# ledDriverSchematic.net
KiCad netlist of a schematic drawn in Altium Designer
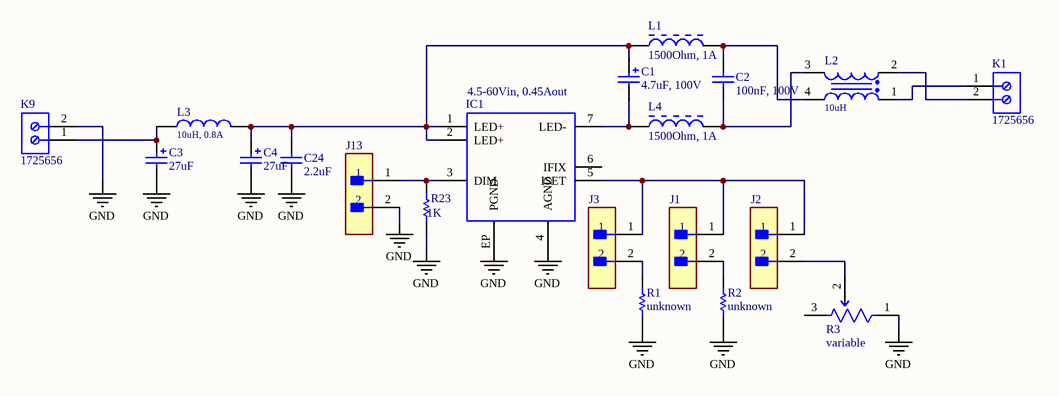
[diagram p0: ledDriverSchematic.SchDoc]

(export (version "E")
  (design (tool "Eeschema 10.0.6"))
  (components
    (comp (ref "C1")
      (value "4.7uF, 100V")
      (footprint "WCAP-PSLP_D6.3H7.7")
      (description "WCAP-PSLP Aluminum Polymer Capacitor, V-Chip, SMT, D6.3xH7.7mm, 4.7uF, 100V")
      (fields
        (field (name "MANUFACTURER PART NUMBER") "875105945001")
        (field (name "MANUFACTURER") "Wurth Elektronik")
      )
      (libsource (lib "Altium_WCAP-PSLP (rev20b)") (part "875105945001"))
    )
    (comp (ref "C2")
      (value "100nF, 100V")
      (footprint "WCAP-CSGP_0805_H=1.25mm")
      (description "WCAP-CSGP Multilayer Ceramic Chip Capacitor, General Purpose, size 0805, X7R, 100nF, 100V")
      (fields
        (field (name "MANUFACTURER PART NUMBER") "885012207128")
        (field (name "MANUFACTURER") "Wurth Elektronik")
      )
      (libsource (lib "Altium_WCAP-CSGP (rev21a)") (part "885012207128"))
    )
    (comp (ref "C3")
      (value "27uF")
      (footprint "WCAP-ATUL_D8H11.5")
      (description "WCAP-ATUL Aluminum Electrolytic Capacitor, Radial, THT, D8xH11.5mm, 27uF, 100V")
      (fields
        (field (name "MANUFACTURER") "Wurth Elektronik")
        (field (name "MANUFACTURER PART NUMBER") "860040874001")
      )
      (libsource (lib "Altium_WCAP-ATUL (rev20b)") (part "860040874001"))
    )
    (comp (ref "C4")
      (value "27uF")
      (footprint "WCAP-ATUL_D8H11.5")
      (description "WCAP-ATUL Aluminum Electrolytic Capacitor, Radial, THT, D8xH11.5mm, 27uF, 100V")
      (fields
        (field (name "MANUFACTURER") "Wurth Elektronik")
        (field (name "MANUFACTURER PART NUMBER") "860040874001")
      )
      (libsource (lib "Altium_WCAP-ATUL (rev20b)") (part "860040874001"))
    )
    (comp (ref "C24")
      (value "2.2uF")
      (footprint "CAPC1210(3225)280_N")
      (description "CAP 2.2uF 100V ±10% 1210 (3225 Metric) Thickness 2.8mm SMD")
      (fields (field (name "TOLERANCE") "Â±10%"))
      (libsource (lib "Altium Content Vault") (part "CAP"))
    )
    (comp (ref "IC1")
      (value "4.5-60Vin, 0.45Aout")
      (footprint "172946001")
      (description "MagI3C-LDHM LED Step Down High Current Module, TO263-7EP, 4.5-60Vin, 0.45Aout")
      (fields (field (name "PART NUMBER") "172946001") (field (name "PUBLISHER") "Wurth Elektronik"))
      (libsource (lib "Altium_MAGIC-LDHM (rev19a)") (part "172946001"))
    )
    (comp (ref "J1")
      (value "~")
      (footprint "FP-TSW-102-07-G-S-MFG")
      (description "CONN HEADER VERT 2POS 2.54MM")
      (fields
        (field (name "MANUFACTURER") "Samtec")
        (field (name "MANUFACTURER PART NUMBER") "TSW-102-07-G-S")
      )
      (libsource (lib "Altium Content Vault") (part "3bc925449376181038e59eaffc5286c"))
    )
    (comp (ref "J2")
      (value "~")
      (footprint "FP-TSW-102-07-G-S-MFG")
      (description "CONN HEADER VERT 2POS 2.54MM")
      (fields
        (field (name "MANUFACTURER") "Samtec")
        (field (name "MANUFACTURER PART NUMBER") "TSW-102-07-G-S")
      )
      (libsource (lib "Altium Content Vault") (part "3bc925449376181038e59eaffc5286c"))
    )
    (comp (ref "J3")
      (value "~")
      (footprint "FP-TSW-102-07-G-S-MFG")
      (description "CONN HEADER VERT 2POS 2.54MM")
      (fields
        (field (name "MANUFACTURER") "Samtec")
        (field (name "MANUFACTURER PART NUMBER") "TSW-102-07-G-S")
      )
      (libsource (lib "Altium Content Vault") (part "3bc925449376181038e59eaffc5286c"))
    )
    (comp (ref "J13")
      (value "~")
      (footprint "FP-TSW-102-07-G-S-MFG")
      (description "CONN HEADER VERT 2POS 2.54MM")
      (fields
        (field (name "MANUFACTURER") "Samtec")
        (field (name "MANUFACTURER PART NUMBER") "TSW-102-07-G-S")
      )
      (libsource (lib "Altium Content Vault") (part "3bc925449376181038e59eaffc5286c"))
    )
    (comp (ref "K1")
      (value "1725656")
      (footprint "PHOE-1725656-2")
      (description "Male Header, Pitch 2.54 mm, 1 x 2 Position, Height 9 mm, Tail Length 3.5 mm")
      (fields (field (name "MANUFACTURER") "Phoenix Contact"))
      (libsource (lib "Altium Content Vault") (part "CN-1P-F-TB2"))
    )
    (comp (ref "K9")
      (value "1725656")
      (footprint "PHOE-1725656-2")
      (description "Male Header, Pitch 2.54 mm, 1 x 2 Position, Height 9 mm, Tail Length 3.5 mm")
      (fields (field (name "MANUFACTURER") "Phoenix Contact"))
      (libsource (lib "Altium Content Vault") (part "CN-1P-F-TB2"))
    )
    (comp (ref "L1")
      (value "1500Ohm, 1A")
      (footprint "WE-CBF_0805_High Current")
      (description "WE-CBF SMT EMI Suppression Ferrite Bead, size 0805, 1500Ohm, 1A")
      (fields
        (field (name "MANUFACTURER PART NUMBER") "742792097")
        (field (name "MANUFACTURER") "Wurth Elektronik")
      )
      (libsource (lib "WE-CBF (rev20b)") (part "742792097"))
    )
    (comp (ref "L2")
      (value "10uH")
      (footprint "WE-SL2")
      (description "WE-SL2 SMT Common Mode Line Filter, 10uH, 1.6A, 80V")
      (fields
        (field (name "MANUFACTURER PART NUMBER") "744226S")
        (field (name "MANUFACTURER") "Wurth Elektronik")
      )
      (libsource (lib "WE-SL2 (rev20b)") (part "744226S"))
    )
    (comp (ref "L3")
      (value "10uH, 0.8A")
      (footprint "WE-PD2_3521")
      (description "WE-PD2 SMT Power Inductor, size 3521, 10uH, 0.8A")
      (fields
        (field (name "MANUFACTURER") "Wurth Elektronik")
        (field (name "MANUFACTURER PART NUMBER") "7447732110")
      )
      (libsource (lib "WE-PD2 (rev20a)") (part "7447732110"))
    )
    (comp (ref "L4")
      (value "1500Ohm, 1A")
      (footprint "WE-CBF_0805_High Current")
      (description "WE-CBF SMT EMI Suppression Ferrite Bead, size 0805, 1500Ohm, 1A")
      (fields
        (field (name "MANUFACTURER PART NUMBER") "742792097")
        (field (name "MANUFACTURER") "Wurth Elektronik")
      )
      (libsource (lib "WE-CBF (rev20b)") (part "742792097"))
    )
    (comp (ref "R1")
      (value "unknown")
      (footprint "VISH-A1-2_V2")
      (description "Power Metal Film Leaded Resistor, 62 KOhm +/-5%, 2 W, 2-Pin THD, RoHS, Ammo Pack")
      (fields (field (name "TOLERANCE") "+/-5%") (field (name "POWER") "2 W"))
      (libsource (lib "Altium Content Vault") (part "VISH-RES-2"))
    )
    (comp (ref "R2")
      (value "unknown")
      (footprint "VISH-A1-2_V2")
      (description "Power Metal Film Leaded Resistor, 62 KOhm +/-5%, 2 W, 2-Pin THD, RoHS, Ammo Pack")
      (fields (field (name "TOLERANCE") "+/-5%") (field (name "POWER") "2 W"))
      (libsource (lib "Altium Content Vault") (part "VISH-RES-2"))
    )
    (comp (ref "R3")
      (value "variable")
      (footprint "FP-3361P-MFG")
      (description "TRIMMER 5K OHM 0.5W GW TOP ADJ")
      (fields
        (field (name "OCTOPART") "https://octopart.com/3361p-1-502glf-bourns-92301")
        (field (name "TOLERANCE") "10%")
      )
      (libsource (lib "Altium Content Vault") (part "2dcfd2547301a7d3209a5e99acfd772"))
    )
    (comp (ref "R23")
      (value "1K")
      (footprint "RESC2013X60X30ML20T20")
      (fields (field (name "PART NUMBER") "RK73B2ATTD102J") (field (name "MANUFACTURER") "KOA Speer"))
      (libsource (lib "Altium Content Vault") (part "RES"))
    )
  )
  (nets
    (net (code "1") (name "GND") (class "Default")
      (node (ref "C24") (pin "1") (pinfunction "1_1") (pintype "passive"))
      (node (ref "C3") (pin "2") (pinfunction "N_2") (pintype "passive"))
      (node (ref "C4") (pin "2") (pinfunction "N_2") (pintype "passive"))
      (node (ref "IC1") (pin "4") (pinfunction "AGND_4") (pintype "passive"))
      (node (ref "IC1") (pin "EP") (pinfunction "PGND_EP") (pintype "passive"))
      (node (ref "J13") (pin "2") (pinfunction "2_2") (pintype "passive"))
      (node (ref "K9") (pin "2") (pinfunction "2_2") (pintype "passive"))
      (node (ref "R1") (pin "1") (pinfunction "1_1") (pintype "passive"))
      (node (ref "R2") (pin "1") (pinfunction "1_1") (pintype "passive"))
      (node (ref "R23") (pin "1") (pinfunction "1_1") (pintype "passive"))
      (node (ref "R3") (pin "1") (pinfunction "CCW_1") (pintype "passive"))
    )
    (net (code "2") (name "Net-(C1-N)") (class "Default")
      (node (ref "C1") (pin "2") (pinfunction "N_2") (pintype "passive"))
      (node (ref "IC1") (pin "7") (pinfunction "LED-_7") (pintype "passive"))
      (node (ref "L4") (pin "1") (pinfunction "1_1") (pintype "passive"))
    )
    (net (code "3") (name "Net-(C1-P)") (class "Default")
      (node (ref "C1") (pin "1") (pinfunction "P_1") (pintype "passive"))
      (node (ref "C24") (pin "2") (pinfunction "2_2") (pintype "passive"))
      (node (ref "C4") (pin "1") (pinfunction "P_1") (pintype "passive"))
      (node (ref "IC1") (pin "1") (pinfunction "LED+_1") (pintype "passive"))
      (node (ref "IC1") (pin "2") (pinfunction "LED+_2") (pintype "passive"))
      (node (ref "L1") (pin "1") (pinfunction "1_1") (pintype "passive"))
      (node (ref "L3") (pin "2") (pinfunction "2_2") (pintype "passive"))
    )
    (net (code "4") (name "Net-(C2-Pad1)") (class "Default")
      (node (ref "C2") (pin "1") (pinfunction "1_1") (pintype "passive"))
      (node (ref "L2") (pin "3") (pinfunction "3_3") (pintype "passive"))
      (node (ref "L4") (pin "2") (pinfunction "2_2") (pintype "passive"))
    )
    (net (code "5") (name "Net-(C2-Pad2)") (class "Default")
      (node (ref "C2") (pin "2") (pinfunction "2_2") (pintype "passive"))
      (node (ref "L1") (pin "2") (pinfunction "2_2") (pintype "passive"))
      (node (ref "L2") (pin "4") (pinfunction "4_4") (pintype "passive"))
    )
    (net (code "6") (name "Net-(C3-P)") (class "Default")
      (node (ref "C3") (pin "1") (pinfunction "P_1") (pintype "passive"))
      (node (ref "K9") (pin "1") (pinfunction "1_1") (pintype "passive"))
      (node (ref "L3") (pin "1") (pinfunction "1_1") (pintype "passive"))
    )
    (net (code "7") (name "Net-(IC1-DIM)") (class "Default")
      (node (ref "IC1") (pin "3") (pinfunction "DIM_3") (pintype "passive"))
      (node (ref "J13") (pin "1") (pinfunction "1_1") (pintype "passive"))
      (node (ref "R23") (pin "2") (pinfunction "2_2") (pintype "passive"))
    )
    (net (code "8") (name "Net-(IC1-ISET)") (class "Default")
      (node (ref "IC1") (pin "5") (pinfunction "ISET_5") (pintype "passive"))
      (node (ref "J1") (pin "1") (pinfunction "1_1") (pintype "passive"))
      (node (ref "J2") (pin "1") (pinfunction "1_1") (pintype "passive"))
      (node (ref "J3") (pin "1") (pinfunction "1_1") (pintype "passive"))
    )
    (net (code "9") (name "Net-(J1-Pad2)") (class "Default")
      (node (ref "J1") (pin "2") (pinfunction "2_2") (pintype "passive"))
      (node (ref "R2") (pin "2") (pinfunction "2_2") (pintype "passive"))
    )
    (net (code "10") (name "Net-(J3-Pad2)") (class "Default")
      (node (ref "J3") (pin "2") (pinfunction "2_2") (pintype "passive"))
      (node (ref "R1") (pin "2") (pinfunction "2_2") (pintype "passive"))
    )
    (net (code "11") (name "Net-(K1-Pad1)") (class "Default")
      (node (ref "K1") (pin "1") (pinfunction "1_1") (pintype "passive"))
      (node (ref "L2") (pin "1") (pinfunction "1_1") (pintype "passive"))
    )
    (net (code "12") (name "Net-(K1-Pad2)") (class "Default")
      (node (ref "K1") (pin "2") (pinfunction "2_2") (pintype "passive"))
      (node (ref "L2") (pin "2") (pinfunction "2_2") (pintype "passive"))
    )
    (net (code "13") (name "Net-(R3-WIPER)") (class "Default")
      (node (ref "J2") (pin "2") (pinfunction "2_2") (pintype "passive"))
      (node (ref "R3") (pin "2") (pinfunction "WIPER_2") (pintype "passive"))
    )
    (net (code "14") (name "unconnected-(IC1-IFIX-Pad6)") (class "Default")
      (node (ref "IC1") (pin "6") (pinfunction "IFIX_6") (pintype "passive"))
    )
    (net (code "15") (name "unconnected-(R3-CW-Pad3)") (class "Default")
      (node (ref "R3") (pin "3") (pinfunction "CW_3") (pintype "passive"))
    )
  )
)
